# MotorController.net
KiCad netlist of a schematic drawn in EAGLE
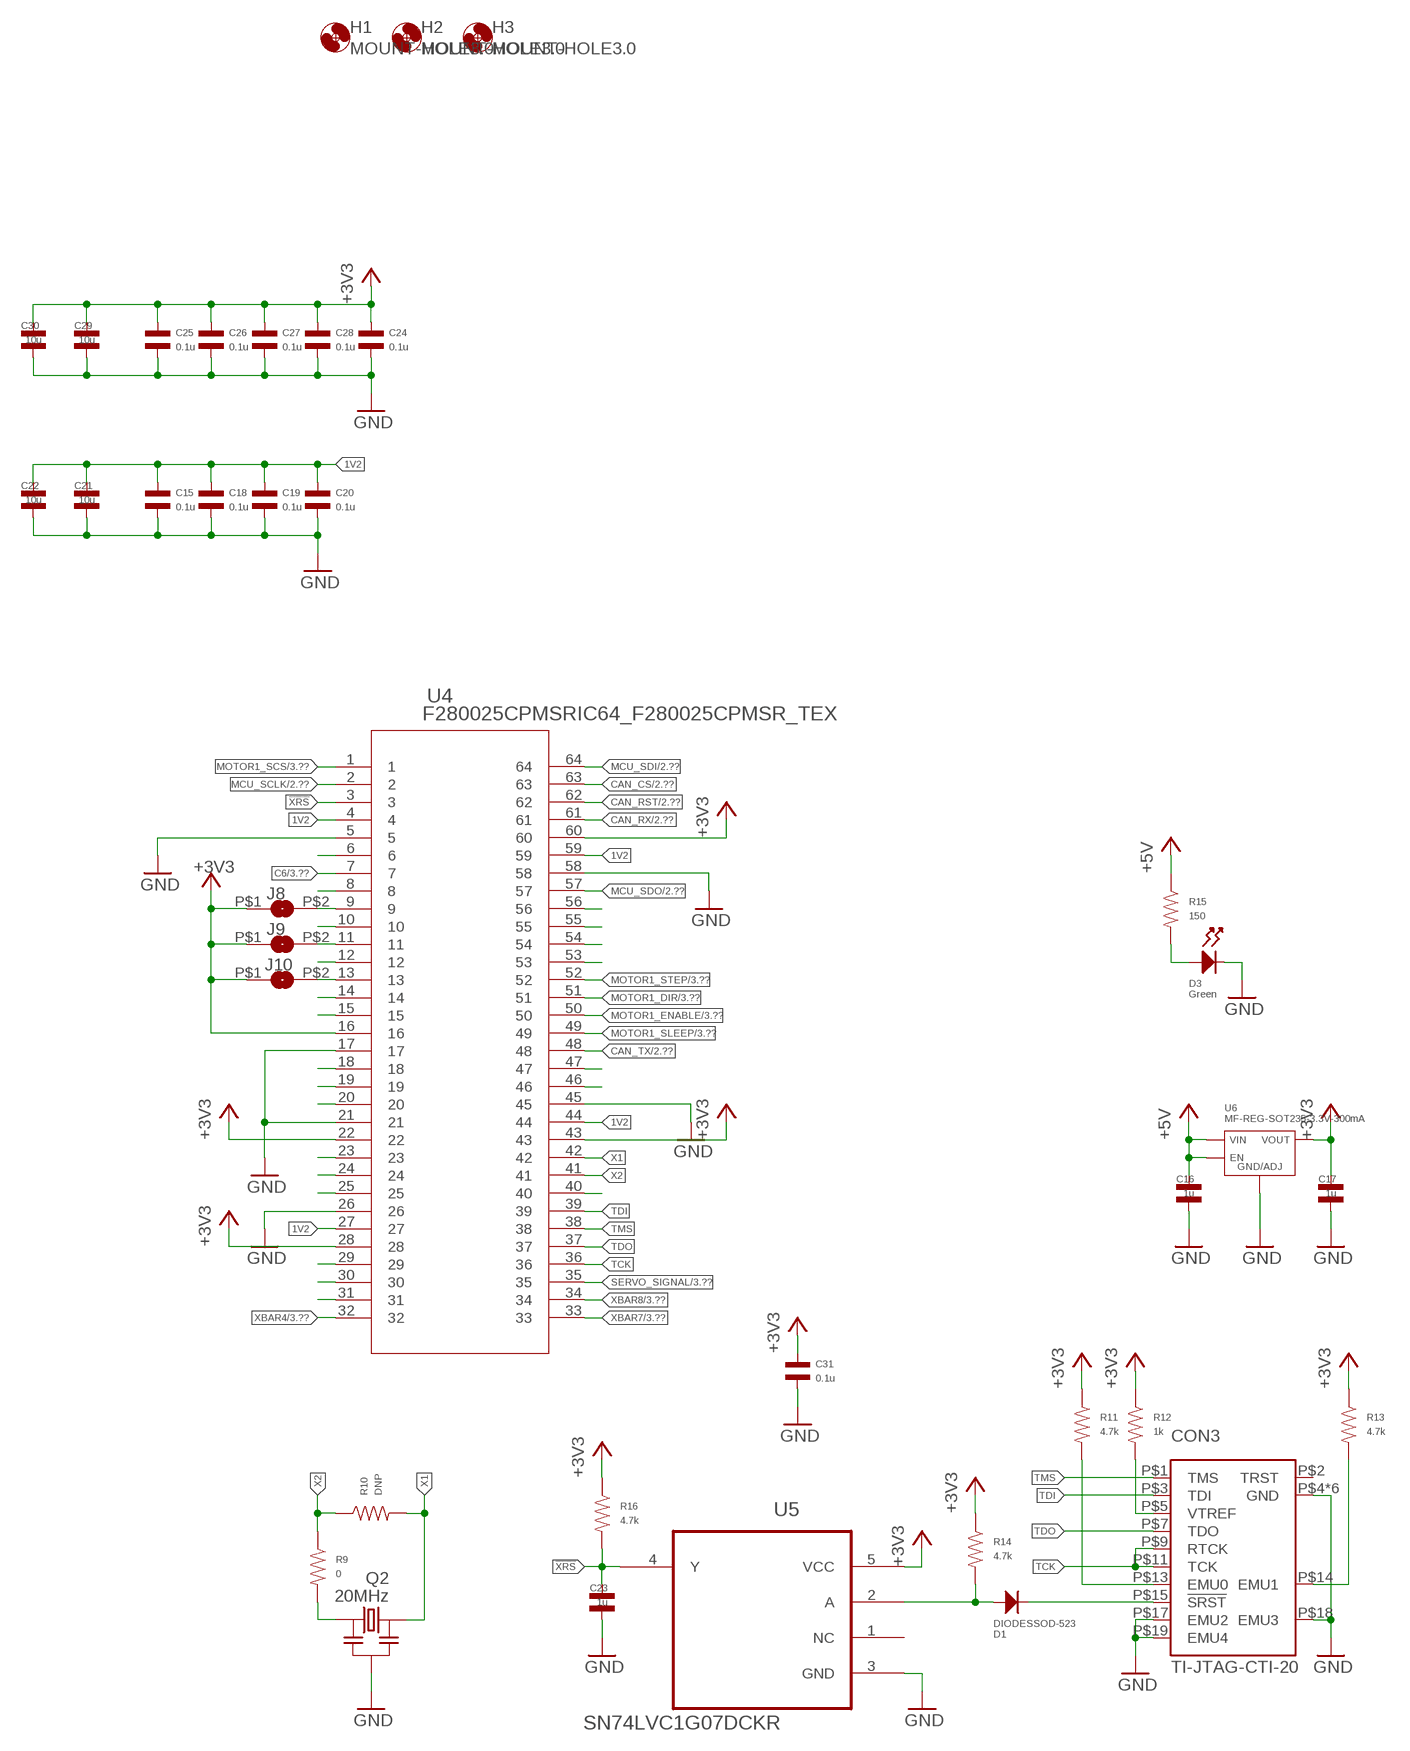
[diagram p0: schematic, sheet 1]
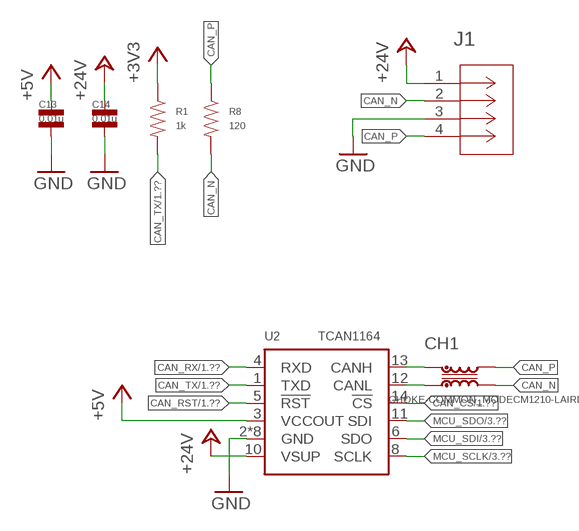
[diagram p1: schematic, sheet 2]
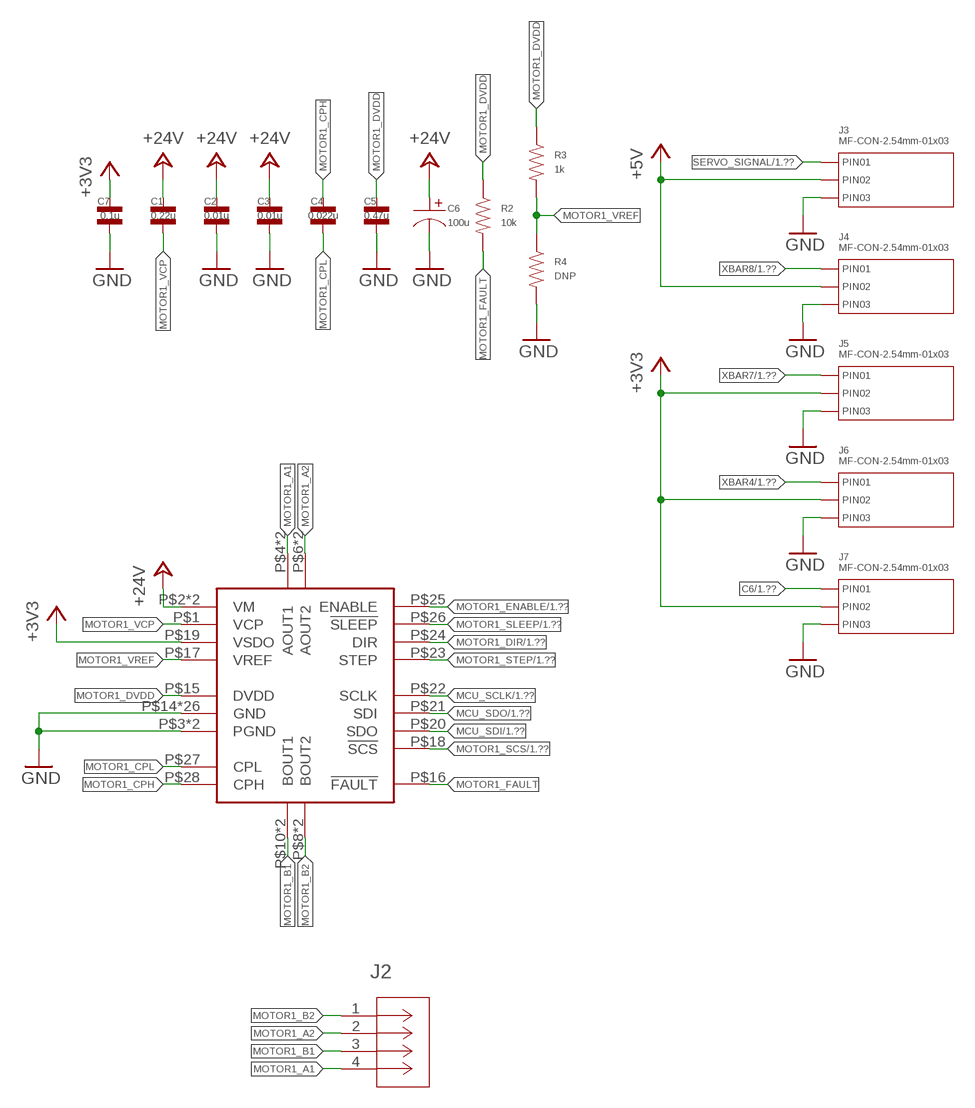
[diagram p2: schematic, sheet 3]

(export (version "E")
  (design (tool "Eeschema 10.0.6"))
  (components
    (comp (ref "C15")
      (value "0.1u")
      (footprint "eagle-import:C0402")
      (fields (field (name "MPN") "GCM155R71H104KE02D"))
      (libsource (lib "eagle-import") (part "CAPACITOR_NP_0402"))
    )
    (comp (ref "C16")
      (value "1u")
      (footprint "eagle-import:C0805")
      (fields (field (name "MPN") "CL21B105KAFNNNE"))
      (libsource (lib "eagle-import") (part "CAPACITOR_NP_0805"))
    )
    (comp (ref "C17")
      (value "1u")
      (footprint "eagle-import:C0805")
      (fields (field (name "MPN") "CL21B105KAFNNNE"))
      (libsource (lib "eagle-import") (part "CAPACITOR_NP_0805"))
    )
    (comp (ref "C18")
      (value "0.1u")
      (footprint "eagle-import:C0402")
      (fields (field (name "MPN") "GCM155R71H104KE02D"))
      (libsource (lib "eagle-import") (part "CAPACITOR_NP_0402"))
    )
    (comp (ref "C19")
      (value "0.1u")
      (footprint "eagle-import:C0402")
      (fields (field (name "MPN") "GCM155R71H104KE02D"))
      (libsource (lib "eagle-import") (part "CAPACITOR_NP_0402"))
    )
    (comp (ref "C20")
      (value "0.1u")
      (footprint "eagle-import:C0402")
      (fields (field (name "MPN") "GCM155R71H104KE02D"))
      (libsource (lib "eagle-import") (part "CAPACITOR_NP_0402"))
    )
    (comp (ref "C21")
      (value "10u")
      (footprint "eagle-import:C0805")
      (fields (field (name "MPN") "CL21A106KAYNNNE"))
      (libsource (lib "eagle-import") (part "CAPACITOR_NP_0805"))
    )
    (comp (ref "C22")
      (value "10u")
      (footprint "eagle-import:C0805")
      (fields (field (name "MPN") "CL21A106KAYNNNE"))
      (libsource (lib "eagle-import") (part "CAPACITOR_NP_0805"))
    )
    (comp (ref "C23")
      (value "1u")
      (footprint "eagle-import:C0402")
      (fields (field (name "MPN") "CL05A105KA5NQNC"))
      (libsource (lib "eagle-import") (part "CAPACITOR_NP_0402"))
    )
    (comp (ref "C24")
      (value "0.1u")
      (footprint "eagle-import:C0402")
      (fields (field (name "MPN") "GCM155R71H104KE02D"))
      (libsource (lib "eagle-import") (part "CAPACITOR_NP_0402"))
    )
    (comp (ref "C25")
      (value "0.1u")
      (footprint "eagle-import:C0402")
      (fields (field (name "MPN") "GCM155R71H104KE02D"))
      (libsource (lib "eagle-import") (part "CAPACITOR_NP_0402"))
    )
    (comp (ref "C26")
      (value "0.1u")
      (footprint "eagle-import:C0402")
      (fields (field (name "MPN") "GCM155R71H104KE02D"))
      (libsource (lib "eagle-import") (part "CAPACITOR_NP_0402"))
    )
    (comp (ref "C27")
      (value "0.1u")
      (footprint "eagle-import:C0402")
      (fields (field (name "MPN") "GCM155R71H104KE02D"))
      (libsource (lib "eagle-import") (part "CAPACITOR_NP_0402"))
    )
    (comp (ref "C28")
      (value "0.1u")
      (footprint "eagle-import:C0402")
      (fields (field (name "MPN") "GCM155R71H104KE02D"))
      (libsource (lib "eagle-import") (part "CAPACITOR_NP_0402"))
    )
    (comp (ref "C29")
      (value "10u")
      (footprint "eagle-import:C0805")
      (fields (field (name "MPN") "CL21A106KAYNNNE"))
      (libsource (lib "eagle-import") (part "CAPACITOR_NP_0805"))
    )
    (comp (ref "C30")
      (value "10u")
      (footprint "eagle-import:C0805")
      (fields (field (name "MPN") "CL21A106KAYNNNE"))
      (libsource (lib "eagle-import") (part "CAPACITOR_NP_0805"))
    )
    (comp (ref "C31")
      (value "0.1u")
      (footprint "eagle-import:C0402")
      (fields (field (name "MPN") "GCM155R71H104KE02D"))
      (libsource (lib "eagle-import") (part "MF_Passives_4704077_CAPACITOR_NP_0402"))
    )
    (comp (ref "CON3")
      (value "TI-JTAG-CTI-20")
      (footprint "eagle-import:FTR-110-51-L-D-06")
      (fields (field (name "MPN") "FTR-110-51-L-D-06"))
      (libsource (lib "eagle-import") (part "TI-JTAG-CTI-20"))
    )
    (comp (ref "D1")
      (value "DIODESSOD-523")
      (footprint "eagle-import:SOD523")
      (fields (field (name "MPN") "RB510SM-40FHT2R"))
      (libsource (lib "eagle-import") (part "DIODESSOD-523"))
    )
    (comp (ref "D3")
      (value "Green")
      (footprint "eagle-import:LED0603")
      (fields (field (name "HOUSEPART") "NO") (field (name "MPN") "SML-E12P8WT86"))
      (libsource (lib "eagle-import") (part "LED_SINGLE-0603"))
    )
    (comp (ref "H1")
      (value "MOUNT-HOLE3.0")
      (footprint "eagle-import:3,0")
      (libsource (lib "eagle-import") (part "MOUNT-HOLE3.0"))
    )
    (comp (ref "H2")
      (value "MOUNT-HOLE3.0")
      (footprint "eagle-import:3,0")
      (libsource (lib "eagle-import") (part "MOUNT-HOLE3.0"))
    )
    (comp (ref "H3")
      (value "MOUNT-HOLE3.0")
      (footprint "eagle-import:3,0")
      (libsource (lib "eagle-import") (part "MOUNT-HOLE3.0"))
    )
    (comp (ref "J8")
      (value "JUMPER")
      (footprint "eagle-import:SJ")
      (libsource (lib "eagle-import") (part "JUMPER"))
    )
    (comp (ref "J9")
      (value "JUMPER")
      (footprint "eagle-import:SJ")
      (libsource (lib "eagle-import") (part "JUMPER"))
    )
    (comp (ref "J10")
      (value "JUMPER")
      (footprint "eagle-import:SJ")
      (libsource (lib "eagle-import") (part "JUMPER"))
    )
    (comp (ref "Q2")
      (value "20MHz")
      (footprint "eagle-import:CSTNE")
      (fields (field (name "MPN") "CSTNE20M0V53C000R0"))
      (libsource (lib "eagle-import") (part "RESONATORCSTNE"))
    )
    (comp (ref "R9")
      (value "0")
      (footprint "eagle-import:R0402")
      (fields (field (name "MPN") "ERJ-2GE0R00X"))
      (libsource (lib "eagle-import") (part "RESISTOR_0402"))
    )
    (comp (ref "R10")
      (value "DNP")
      (footprint "eagle-import:R0402")
      (libsource (lib "eagle-import") (part "RESISTOR_0402"))
    )
    (comp (ref "R11")
      (value "4.7k")
      (footprint "eagle-import:R0402")
      (fields (field (name "MPN") "ERJ-2RKF4701X"))
      (libsource (lib "eagle-import") (part "RESISTOR_0402"))
    )
    (comp (ref "R12")
      (value "1k")
      (footprint "eagle-import:R0402")
      (fields (field (name "MPN") "ERJ-2RKF1001X"))
      (libsource (lib "eagle-import") (part "RESISTOR_0402"))
    )
    (comp (ref "R13")
      (value "4.7k")
      (footprint "eagle-import:R0402")
      (fields (field (name "MPN") "ERJ-2RKF4701X"))
      (libsource (lib "eagle-import") (part "RESISTOR_0402"))
    )
    (comp (ref "R14")
      (value "4.7k")
      (footprint "eagle-import:R0402")
      (fields (field (name "MPN") "ERJ-2RKF4701X"))
      (libsource (lib "eagle-import") (part "RESISTOR_0402"))
    )
    (comp (ref "R15")
      (value "150")
      (footprint "eagle-import:R0805")
      (fields (field (name "MPN") "ERJ-6GEYJ151V"))
      (libsource (lib "eagle-import") (part "RESISTOR_0805"))
    )
    (comp (ref "R16")
      (value "4.7k")
      (footprint "eagle-import:R0402")
      (fields (field (name "MPN") "ERJ-2RKF4701X"))
      (libsource (lib "eagle-import") (part "RESISTOR_0402"))
    )
    (comp (ref "U4")
      (value "F280025CPMSRIC64_F280025CPMSR_TEX")
      (footprint "eagle-import:IC64_F280025CPMSR_TEX")
      (fields
        (field (name "MANUFACTURER_PART_NUMBER") "F280025CPMSR")
        (field (name "COPYRIGHT") "Copyright (C) 2024 Ultra Librarian. All rights reserved.")
      )
      (libsource (lib "eagle-import") (part "F280025CPMSRIC64_F280025CPMSR_TEX"))
    )
    (comp (ref "U5")
      (value "SN74LVC1G07DCKR")
      (footprint "eagle-import:SOT65P210X110-5N")
      (libsource (lib "eagle-import") (part "SN74LVC1G07DCKR"))
    )
    (comp (ref "U6")
      (value "MF-REG-SOT235-3.3V-300mA")
      (footprint "eagle-import:SOT-23-5")
      (fields (field (name "HOUSEPART") "YES") (field (name "MPN") "TLV70233PDBVR"))
      (libsource (lib "eagle-import") (part "TLV70233PDBVR"))
    )
    (comp (ref "C13")
      (value "0.01u")
      (footprint "eagle-import:C0402")
      (fields (field (name "MPN") "CL05B103KB5NNNC"))
      (libsource (lib "eagle-import") (part "CAPACITOR_NP_0402"))
    )
    (comp (ref "C14")
      (value "0.01u")
      (footprint "eagle-import:C0402")
      (fields (field (name "MPN") "CL05B103KB5NNNC"))
      (libsource (lib "eagle-import") (part "CAPACITOR_NP_0402"))
    )
    (comp (ref "CH1")
      (value "CHOKE-COMMON_MODECM1210-LAIRD")
      (footprint "eagle-import:CM1210-LAIRD")
      (fields (field (name "MPN") "CM1210B104R-1A"))
      (libsource (lib "eagle-import") (part "CHOKE-COMMON_MODECM1210-LAIRD"))
    )
    (comp (ref "J1")
      (value "768250004CON_768250004_MOL")
      (footprint "eagle-import:CON_768250004_MOL")
      (fields
        (field (name "MANUFACTURER_PART_NUMBER") "768250004")
        (field (name "MPN") "0768250004")
        (field (name "COPYRIGHT") "Copyright (C) 2024 Ultra Librarian. All rights reserved.")
      )
      (libsource (lib "eagle-import") (part "768250004CON_768250004_MOL"))
    )
    (comp (ref "R1")
      (value "1k")
      (footprint "eagle-import:R0402")
      (fields (field (name "MPN") "ERJ-2RKF1001X"))
      (libsource (lib "eagle-import") (part "RESISTOR_0402"))
    )
    (comp (ref "R8")
      (value "120")
      (footprint "eagle-import:R0402")
      (fields (field (name "MPN") "ERJ-2GEJ121X"))
      (libsource (lib "eagle-import") (part "RESISTOR_0402"))
    )
    (comp (ref "U2")
      (value "TCAN1164")
      (footprint "eagle-import:CONV_TPS63021DSJ")
      (fields (field (name "MPN") "TCAN1164DMTRQ1"))
      (libsource (lib "eagle-import") (part "TCAN1164"))
    )
    (comp (ref "C1")
      (value "0.22u")
      (footprint "eagle-import:C0402")
      (fields (field (name "MPN") "CL05B224KA5VPNC"))
      (libsource (lib "eagle-import") (part "CAPACITOR_NP_0402"))
    )
    (comp (ref "C2")
      (value "0.01u")
      (footprint "eagle-import:C0402")
      (fields (field (name "MPN") "CL05B103KB5NNNC"))
      (libsource (lib "eagle-import") (part "CAPACITOR_NP_0402"))
    )
    (comp (ref "C3")
      (value "0.01u")
      (footprint "eagle-import:C0402")
      (fields (field (name "MPN") "CL05B103KB5NNNC"))
      (libsource (lib "eagle-import") (part "CAPACITOR_NP_0402"))
    )
    (comp (ref "C4")
      (value "0.022u")
      (footprint "eagle-import:C0402")
      (fields (field (name "MPN") "CL05B223KB5VPNC"))
      (libsource (lib "eagle-import") (part "CAPACITOR_NP_0402"))
    )
    (comp (ref "C5")
      (value "0.47u")
      (footprint "eagle-import:C0402")
      (fields (field (name "MPN") "CL05A474KA5NNNC"))
      (libsource (lib "eagle-import") (part "CAPACITOR_NP_0402"))
    )
    (comp (ref "C6")
      (value "100u")
      (footprint "eagle-import:CP6.3MM")
      (fields (field (name "MPN") "MAL218297603E3"))
      (libsource (lib "eagle-import") (part "CAPACITOR_P_6.3MM"))
    )
    (comp (ref "C7")
      (value "0.1u")
      (footprint "eagle-import:C0402")
      (fields (field (name "MPN") "GCM155R71H104KE02D"))
      (libsource (lib "eagle-import") (part "CAPACITOR_NP_0402"))
    )
    (comp (ref "J2")
      (value "768250004CON_768250004_MOL")
      (footprint "eagle-import:CON_768250004_MOL")
      (fields
        (field (name "MANUFACTURER_PART_NUMBER") "768250004")
        (field (name "MPN") "0768250004")
        (field (name "COPYRIGHT") "Copyright (C) 2024 Ultra Librarian. All rights reserved.")
      )
      (libsource (lib "eagle-import") (part "768250004CON_768250004_MOL"))
    )
    (comp (ref "J3")
      (value "MF-CON-2.54mm-01x03")
      (footprint "eagle-import:PTH_2.54MM_01X03")
      (fields (field (name "HOUSEPART") "YES"))
      (libsource (lib "eagle-import") (part "CON_01X03_PTH_2.54MM"))
    )
    (comp (ref "J4")
      (value "MF-CON-2.54mm-01x03")
      (footprint "eagle-import:PTH_2.54MM_01X03")
      (fields (field (name "HOUSEPART") "YES"))
      (libsource (lib "eagle-import") (part "CON_01X03_PTH_2.54MM"))
    )
    (comp (ref "J5")
      (value "MF-CON-2.54mm-01x03")
      (footprint "eagle-import:PTH_2.54MM_01X03")
      (fields (field (name "HOUSEPART") "YES"))
      (libsource (lib "eagle-import") (part "CON_01X03_PTH_2.54MM"))
    )
    (comp (ref "J6")
      (value "MF-CON-2.54mm-01x03")
      (footprint "eagle-import:PTH_2.54MM_01X03")
      (fields (field (name "HOUSEPART") "YES"))
      (libsource (lib "eagle-import") (part "CON_01X03_PTH_2.54MM"))
    )
    (comp (ref "J7")
      (value "MF-CON-2.54mm-01x03")
      (footprint "eagle-import:PTH_2.54MM_01X03")
      (fields (field (name "HOUSEPART") "YES"))
      (libsource (lib "eagle-import") (part "CON_01X03_PTH_2.54MM"))
    )
    (comp (ref "R2")
      (value "10k")
      (footprint "eagle-import:R0402")
      (fields (field (name "MPN") "ERJ-2RKF1002X"))
      (libsource (lib "eagle-import") (part "RESISTOR_0402"))
    )
    (comp (ref "R3")
      (value "1k")
      (footprint "eagle-import:R0402")
      (fields (field (name "MPN") "ERJ-2RKF1001X"))
      (libsource (lib "eagle-import") (part "RESISTOR_0402"))
    )
    (comp (ref "R4")
      (value "DNP")
      (footprint "eagle-import:R0402")
      (libsource (lib "eagle-import") (part "RESISTOR_0402"))
    )
    (comp (ref "U1")
      (value "DRV8434SPWPR")
      (footprint "eagle-import:HTSSOP(PWP)-28")
      (libsource (lib "eagle-import") (part "DRV8434SPWPR"))
    )
  )
  (nets
    (net (code "1") (name "+3V3") (class "Default")
      (node (ref "C17") (pin "P$1") (pinfunction "P$1_P$1") (pintype "passive"))
      (node (ref "C24") (pin "P$1") (pinfunction "P$1_P$1") (pintype "passive"))
      (node (ref "C25") (pin "P$1") (pinfunction "P$1_P$1") (pintype "passive"))
      (node (ref "C26") (pin "P$1") (pinfunction "P$1_P$1") (pintype "passive"))
      (node (ref "C27") (pin "P$1") (pinfunction "P$1_P$1") (pintype "passive"))
      (node (ref "C28") (pin "P$1") (pinfunction "P$1_P$1") (pintype "passive"))
      (node (ref "C29") (pin "P$1") (pinfunction "P$1_P$1") (pintype "passive"))
      (node (ref "C30") (pin "P$1") (pinfunction "P$1_P$1") (pintype "passive"))
      (node (ref "C31") (pin "P$1") (pinfunction "P$1_P$1") (pintype "passive"))
      (node (ref "C7") (pin "P$1") (pinfunction "P$1_P$1") (pintype "passive"))
      (node (ref "J10") (pin "P$1") (pinfunction "1_P$1") (pintype "passive"))
      (node (ref "J5") (pin "P$2") (pinfunction "PIN2_P$2") (pintype "bidirectional"))
      (node (ref "J6") (pin "P$2") (pinfunction "PIN2_P$2") (pintype "bidirectional"))
      (node (ref "J7") (pin "P$2") (pinfunction "PIN2_P$2") (pintype "bidirectional"))
      (node (ref "J8") (pin "P$1") (pinfunction "1_P$1") (pintype "passive"))
      (node (ref "J9") (pin "P$1") (pinfunction "1_P$1") (pintype "passive"))
      (node (ref "R1") (pin "P$1") (pinfunction "P$1_P$1") (pintype "passive"))
      (node (ref "R11") (pin "P$1") (pinfunction "P$1_P$1") (pintype "passive"))
      (node (ref "R12") (pin "P$1") (pinfunction "P$1_P$1") (pintype "passive"))
      (node (ref "R13") (pin "P$1") (pinfunction "P$1_P$1") (pintype "passive"))
      (node (ref "R14") (pin "P$1") (pinfunction "P$1_P$1") (pintype "passive"))
      (node (ref "R16") (pin "P$1") (pinfunction "P$1_P$1") (pintype "passive"))
      (node (ref "U1") (pin "P$19") (pinfunction "VSDO_P$19") (pintype "bidirectional"))
      (node (ref "U4") (pin "16") (pinfunction "16_16") (pintype "passive"))
      (node (ref "U4") (pin "22") (pinfunction "22_22") (pintype "passive"))
      (node (ref "U4") (pin "28") (pinfunction "28_28") (pintype "passive"))
      (node (ref "U4") (pin "43") (pinfunction "43_43") (pintype "passive"))
      (node (ref "U4") (pin "60") (pinfunction "60_60") (pintype "passive"))
      (node (ref "U5") (pin "5") (pinfunction "VCC_5") (pintype "power_in"))
      (node (ref "U6") (pin "P$5") (pinfunction "VOUT_P$5") (pintype "bidirectional"))
    )
    (net (code "2") (name "+5V") (class "Default")
      (node (ref "C13") (pin "P$1") (pinfunction "P$1_P$1") (pintype "passive"))
      (node (ref "C16") (pin "P$1") (pinfunction "P$1_P$1") (pintype "passive"))
      (node (ref "J3") (pin "P$2") (pinfunction "PIN2_P$2") (pintype "bidirectional"))
      (node (ref "J4") (pin "P$2") (pinfunction "PIN2_P$2") (pintype "bidirectional"))
      (node (ref "R15") (pin "P$1") (pinfunction "P$1_P$1") (pintype "passive"))
      (node (ref "U2") (pin "3") (pinfunction "VCCOUT_3") (pintype "bidirectional"))
      (node (ref "U6") (pin "P$1") (pinfunction "VIN_P$1") (pintype "bidirectional"))
      (node (ref "U6") (pin "P$3") (pinfunction "EN_P$3") (pintype "bidirectional"))
    )
    (net (code "3") (name "+24V") (class "Default")
      (node (ref "C1") (pin "P$1") (pinfunction "P$1_P$1") (pintype "passive"))
      (node (ref "C14") (pin "P$1") (pinfunction "P$1_P$1") (pintype "passive"))
      (node (ref "C2") (pin "P$1") (pinfunction "P$1_P$1") (pintype "passive"))
      (node (ref "C3") (pin "P$1") (pinfunction "P$1_P$1") (pintype "passive"))
      (node (ref "C6") (pin "P$1") (pinfunction "P$1_P$1") (pintype "passive"))
      (node (ref "J1") (pin "1") (pinfunction "1_1") (pintype "passive"))
      (node (ref "U1") (pin "P$13") (pinfunction "VM_P$13") (pintype "bidirectional"))
      (node (ref "U1") (pin "P$2") (pinfunction "VM_P$2") (pintype "bidirectional"))
      (node (ref "U2") (pin "10") (pinfunction "VSUP_10") (pintype "bidirectional"))
    )
    (net (code "4") (name "1V2") (class "Default")
      (node (ref "C15") (pin "P$1") (pinfunction "P$1_P$1") (pintype "passive"))
      (node (ref "C18") (pin "P$1") (pinfunction "P$1_P$1") (pintype "passive"))
      (node (ref "C19") (pin "P$1") (pinfunction "P$1_P$1") (pintype "passive"))
      (node (ref "C20") (pin "P$1") (pinfunction "P$1_P$1") (pintype "passive"))
      (node (ref "C21") (pin "P$1") (pinfunction "P$1_P$1") (pintype "passive"))
      (node (ref "C22") (pin "P$1") (pinfunction "P$1_P$1") (pintype "passive"))
      (node (ref "U4") (pin "27") (pinfunction "27_27") (pintype "passive"))
      (node (ref "U4") (pin "4") (pinfunction "4_4") (pintype "passive"))
      (node (ref "U4") (pin "44") (pinfunction "44_44") (pintype "passive"))
      (node (ref "U4") (pin "59") (pinfunction "59_59") (pintype "passive"))
    )
    (net (code "5") (name "C6") (class "Default")
      (node (ref "J7") (pin "P$1") (pinfunction "PIN1_P$1") (pintype "bidirectional"))
      (node (ref "U4") (pin "7") (pinfunction "7_7") (pintype "passive"))
    )
    (net (code "6") (name "CAN_CS") (class "Default")
      (node (ref "U2") (pin "14") (pinfunction "~{CS}_14") (pintype "bidirectional"))
      (node (ref "U4") (pin "63") (pinfunction "63_63") (pintype "passive"))
    )
    (net (code "7") (name "CAN_N") (class "Default")
      (node (ref "CH1") (pin "P$3") (pinfunction "3_P$3") (pintype "bidirectional"))
      (node (ref "J1") (pin "2") (pinfunction "2_2") (pintype "passive"))
      (node (ref "R8") (pin "P$2") (pinfunction "P$2_P$2") (pintype "passive"))
    )
    (net (code "8") (name "CAN_P") (class "Default")
      (node (ref "CH1") (pin "P$2") (pinfunction "2_P$2") (pintype "bidirectional"))
      (node (ref "J1") (pin "4") (pinfunction "4_4") (pintype "passive"))
      (node (ref "R8") (pin "P$1") (pinfunction "P$1_P$1") (pintype "passive"))
    )
    (net (code "9") (name "CAN_RST") (class "Default")
      (node (ref "U2") (pin "5") (pinfunction "~{RST}_5") (pintype "bidirectional"))
      (node (ref "U4") (pin "62") (pinfunction "62_62") (pintype "passive"))
    )
    (net (code "10") (name "CAN_RX") (class "Default")
      (node (ref "U2") (pin "4") (pinfunction "RXD_4") (pintype "bidirectional"))
      (node (ref "U4") (pin "61") (pinfunction "61_61") (pintype "passive"))
    )
    (net (code "11") (name "CAN_TX") (class "Default")
      (node (ref "R1") (pin "P$2") (pinfunction "P$2_P$2") (pintype "passive"))
      (node (ref "U2") (pin "1") (pinfunction "TXD_1") (pintype "bidirectional"))
      (node (ref "U4") (pin "48") (pinfunction "48_48") (pintype "passive"))
    )
    (net (code "12") (name "GND") (class "Default")
      (node (ref "C13") (pin "P$2") (pinfunction "P$2_P$2") (pintype "passive"))
      (node (ref "C14") (pin "P$2") (pinfunction "P$2_P$2") (pintype "passive"))
      (node (ref "C15") (pin "P$2") (pinfunction "P$2_P$2") (pintype "passive"))
      (node (ref "C16") (pin "P$2") (pinfunction "P$2_P$2") (pintype "passive"))
      (node (ref "C17") (pin "P$2") (pinfunction "P$2_P$2") (pintype "passive"))
      (node (ref "C18") (pin "P$2") (pinfunction "P$2_P$2") (pintype "passive"))
      (node (ref "C19") (pin "P$2") (pinfunction "P$2_P$2") (pintype "passive"))
      (node (ref "C2") (pin "P$2") (pinfunction "P$2_P$2") (pintype "passive"))
      (node (ref "C20") (pin "P$2") (pinfunction "P$2_P$2") (pintype "passive"))
      (node (ref "C21") (pin "P$2") (pinfunction "P$2_P$2") (pintype "passive"))
      (node (ref "C22") (pin "P$2") (pinfunction "P$2_P$2") (pintype "passive"))
      (node (ref "C23") (pin "P$2") (pinfunction "P$2_P$2") (pintype "passive"))
      (node (ref "C24") (pin "P$2") (pinfunction "P$2_P$2") (pintype "passive"))
      (node (ref "C25") (pin "P$2") (pinfunction "P$2_P$2") (pintype "passive"))
      (node (ref "C26") (pin "P$2") (pinfunction "P$2_P$2") (pintype "passive"))
      (node (ref "C27") (pin "P$2") (pinfunction "P$2_P$2") (pintype "passive"))
      (node (ref "C28") (pin "P$2") (pinfunction "P$2_P$2") (pintype "passive"))
      (node (ref "C29") (pin "P$2") (pinfunction "P$2_P$2") (pintype "passive"))
      (node (ref "C3") (pin "P$2") (pinfunction "P$2_P$2") (pintype "passive"))
      (node (ref "C30") (pin "P$2") (pinfunction "P$2_P$2") (pintype "passive"))
      (node (ref "C31") (pin "P$2") (pinfunction "P$2_P$2") (pintype "passive"))
      (node (ref "C5") (pin "P$2") (pinfunction "P$2_P$2") (pintype "passive"))
      (node (ref "C6") (pin "P$2") (pinfunction "P$2_P$2") (pintype "passive"))
      (node (ref "C7") (pin "P$2") (pinfunction "P$2_P$2") (pintype "passive"))
      (node (ref "CON3") (pin "P$10") (pinfunction "GND_P$10") (pintype "bidirectional"))
      (node (ref "CON3") (pin "P$12") (pinfunction "GND_P$12") (pintype "bidirectional"))
      (node (ref "CON3") (pin "P$16") (pinfunction "GND_P$16") (pintype "bidirectional"))
      (node (ref "CON3") (pin "P$17") (pinfunction "EMU2_P$17") (pintype "bidirectional"))
      (node (ref "CON3") (pin "P$18") (pinfunction "EMU3_P$18") (pintype "bidirectional"))
      (node (ref "CON3") (pin "P$19") (pinfunction "EMU4_P$19") (pintype "bidirectional"))
      (node (ref "CON3") (pin "P$20") (pinfunction "GND_P$20") (pintype "bidirectional"))
      (node (ref "CON3") (pin "P$4") (pinfunction "GND_P$4") (pintype "bidirectional"))
      (node (ref "CON3") (pin "P$8") (pinfunction "GND_P$8") (pintype "bidirectional"))
      (node (ref "D3") (pin "CATHODE") (pinfunction "CATHODE_CATHODE") (pintype "power_in"))
      (node (ref "J1") (pin "3") (pinfunction "3_3") (pintype "passive"))
      (node (ref "J3") (pin "P$3") (pinfunction "PIN3_P$3") (pintype "bidirectional"))
      (node (ref "J4") (pin "P$3") (pinfunction "PIN3_P$3") (pintype "bidirectional"))
      (node (ref "J5") (pin "P$3") (pinfunction "PIN3_P$3") (pintype "bidirectional"))
      (node (ref "J6") (pin "P$3") (pinfunction "PIN3_P$3") (pintype "bidirectional"))
      (node (ref "J7") (pin "P$3") (pinfunction "PIN3_P$3") (pintype "bidirectional"))
      (node (ref "Q2") (pin "2") (pinfunction "GND_2") (pintype "passive"))
      (node (ref "R4") (pin "P$2") (pinfunction "P$2_P$2") (pintype "passive"))
      (node (ref "U1") (pin "P$12") (pinfunction "PGND_P$12") (pintype "bidirectional"))
      (node (ref "U1") (pin "P$14") (pinfunction "GND_P$14") (pintype "bidirectional"))
      (node (ref "U1") (pin "P$29") (pinfunction "GND_P$29") (pintype "bidirectional"))
      (node (ref "U1") (pin "P$3") (pinfunction "PGND_P$3") (pintype "bidirectional"))
      (node (ref "U1") (pin "P$30") (pinfunction "GND_P$30") (pintype "bidirectional"))
      (node (ref "U1") (pin "P$31") (pinfunction "GND_P$31") (pintype "bidirectional"))
      (node (ref "U1") (pin "P$32") (pinfunction "GND_P$32") (pintype "bidirectional"))
      (node (ref "U1") (pin "P$33") (pinfunction "GND_P$33") (pintype "bidirectional"))
      (node (ref "U1") (pin "P$34") (pinfunction "GND_P$34") (pintype "bidirectional"))
      (node (ref "U1") (pin "P$35") (pinfunction "GND_P$35") (pintype "bidirectional"))
      (node (ref "U1") (pin "P$36") (pinfunction "GND_P$36") (pintype "bidirectional"))
      (node (ref "U1") (pin "P$37") (pinfunction "GND_P$37") (pintype "bidirectional"))
      (node (ref "U1") (pin "P$38") (pinfunction "GND_P$38") (pintype "bidirectional"))
      (node (ref "U1") (pin "P$39") (pinfunction "GND_P$39") (pintype "bidirectional"))
      (node (ref "U1") (pin "P$40") (pinfunction "GND_P$40") (pintype "bidirectional"))
      (node (ref "U1") (pin "P$41") (pinfunction "GND_P$41") (pintype "bidirectional"))
      (node (ref "U1") (pin "P$42") (pinfunction "GND_P$42") (pintype "bidirectional"))
      (node (ref "U1") (pin "P$43") (pinfunction "GND_P$43") (pintype "bidirectional"))
      (node (ref "U1") (pin "P$44") (pinfunction "GND_P$44") (pintype "bidirectional"))
      (node (ref "U1") (pin "P$45") (pinfunction "GND_P$45") (pintype "bidirectional"))
      (node (ref "U1") (pin "P$46") (pinfunction "GND_P$46") (pintype "bidirectional"))
      (node (ref "U1") (pin "P$47") (pinfunction "GND_P$47") (pintype "bidirectional"))
      (node (ref "U1") (pin "P$48") (pinfunction "GND_P$48") (pintype "bidirectional"))
      (node (ref "U1") (pin "P$49") (pinfunction "GND_P$49") (pintype "bidirectional"))
      (node (ref "U1") (pin "P$50") (pinfunction "GND_P$50") (pintype "bidirectional"))
      (node (ref "U1") (pin "P$51") (pinfunction "GND_P$51") (pintype "bidirectional"))
      (node (ref "U1") (pin "P$52") (pinfunction "GND_P$52") (pintype "bidirectional"))
      (node (ref "U1") (pin "P$53") (pinfunction "GND_P$53") (pintype "bidirectional"))
      (node (ref "U2") (pin "15") (pinfunction "GND_15") (pintype "bidirectional"))
      (node (ref "U2") (pin "15_1") (pinfunction "GND_15_1") (pintype "bidirectional"))
      (node (ref "U2") (pin "15_2") (pinfunction "GND_15_2") (pintype "bidirectional"))
      (node (ref "U2") (pin "15_3") (pinfunction "GND_15_3") (pintype "bidirectional"))
      (node (ref "U2") (pin "15_4") (pinfunction "GND_15_4") (pintype "bidirectional"))
      (node (ref "U2") (pin "15_5") (pinfunction "GND_15_5") (pintype "bidirectional"))
      (node (ref "U2") (pin "15_6") (pinfunction "GND_15_6") (pintype "bidirectional"))
      (node (ref "U2") (pin "2") (pinfunction "GND_2") (pintype "bidirectional"))
      (node (ref "U4") (pin "17") (pinfunction "17_17") (pintype "passive"))
      (node (ref "U4") (pin "21") (pinfunction "21_21") (pintype "passive"))
      (node (ref "U4") (pin "26") (pinfunction "26_26") (pintype "passive"))
      (node (ref "U4") (pin "45") (pinfunction "45_45") (pintype "passive"))
      (node (ref "U4") (pin "5") (pinfunction "5_5") (pintype "passive"))
      (node (ref "U4") (pin "58") (pinfunction "58_58") (pintype "passive"))
      (node (ref "U5") (pin "3") (pinfunction "GND_3") (pintype "passive"))
      (node (ref "U6") (pin "P$2") (pinfunction "GND/ADJ_P$2") (pintype "bidirectional"))
    )
    (net (code "13") (name "MCU_SCLK") (class "Default")
      (node (ref "U1") (pin "P$22") (pinfunction "SCLK_P$22") (pintype "bidirectional"))
      (node (ref "U2") (pin "8") (pinfunction "SCLK_8") (pintype "bidirectional"))
      (node (ref "U4") (pin "2") (pinfunction "2_2") (pintype "passive"))
    )
    (net (code "14") (name "MCU_SDI") (class "Default")
      (node (ref "U1") (pin "P$20") (pinfunction "SDO_P$20") (pintype "bidirectional"))
      (node (ref "U2") (pin "6") (pinfunction "SDO_6") (pintype "bidirectional"))
      (node (ref "U4") (pin "64") (pinfunction "64_64") (pintype "passive"))
    )
    (net (code "15") (name "MCU_SDO") (class "Default")
      (node (ref "U1") (pin "P$21") (pinfunction "SDI_P$21") (pintype "bidirectional"))
      (node (ref "U2") (pin "11") (pinfunction "SDI_11") (pintype "bidirectional"))
      (node (ref "U4") (pin "57") (pinfunction "57_57") (pintype "passive"))
    )
    (net (code "16") (name "MOTOR1_A1") (class "Default")
      (node (ref "J2") (pin "4") (pinfunction "4_4") (pintype "passive"))
      (node (ref "U1") (pin "P$4") (pinfunction "AOUT1_P$4") (pintype "bidirectional"))
      (node (ref "U1") (pin "P$5") (pinfunction "AOUT1_P$5") (pintype "bidirectional"))
    )
    (net (code "17") (name "MOTOR1_A2") (class "Default")
      (node (ref "J2") (pin "2") (pinfunction "2_2") (pintype "passive"))
      (node (ref "U1") (pin "P$6") (pinfunction "AOUT2_P$6") (pintype "bidirectional"))
      (node (ref "U1") (pin "P$7") (pinfunction "AOUT2_P$7") (pintype "bidirectional"))
    )
    (net (code "18") (name "MOTOR1_B1") (class "Default")
      (node (ref "J2") (pin "3") (pinfunction "3_3") (pintype "passive"))
      (node (ref "U1") (pin "P$10") (pinfunction "BOUT1_P$10") (pintype "bidirectional"))
      (node (ref "U1") (pin "P$11") (pinfunction "BOUT1_P$11") (pintype "bidirectional"))
    )
    (net (code "19") (name "MOTOR1_B2") (class "Default")
      (node (ref "J2") (pin "1") (pinfunction "1_1") (pintype "passive"))
      (node (ref "U1") (pin "P$8") (pinfunction "BOUT2_P$8") (pintype "bidirectional"))
      (node (ref "U1") (pin "P$9") (pinfunction "BOUT2_P$9") (pintype "bidirectional"))
    )
    (net (code "20") (name "MOTOR1_CPH") (class "Default")
      (node (ref "C4") (pin "P$1") (pinfunction "P$1_P$1") (pintype "passive"))
      (node (ref "U1") (pin "P$28") (pinfunction "CPH_P$28") (pintype "bidirectional"))
    )
    (net (code "21") (name "MOTOR1_CPL") (class "Default")
      (node (ref "C4") (pin "P$2") (pinfunction "P$2_P$2") (pintype "passive"))
      (node (ref "U1") (pin "P$27") (pinfunction "CPL_P$27") (pintype "bidirectional"))
    )
    (net (code "22") (name "MOTOR1_DIR") (class "Default")
      (node (ref "U1") (pin "P$24") (pinfunction "DIR_P$24") (pintype "bidirectional"))
      (node (ref "U4") (pin "51") (pinfunction "51_51") (pintype "passive"))
    )
    (net (code "23") (name "MOTOR1_DVDD") (class "Default")
      (node (ref "C5") (pin "P$1") (pinfunction "P$1_P$1") (pintype "passive"))
      (node (ref "R2") (pin "P$1") (pinfunction "P$1_P$1") (pintype "passive"))
      (node (ref "R3") (pin "P$1") (pinfunction "P$1_P$1") (pintype "passive"))
      (node (ref "U1") (pin "P$15") (pinfunction "DVDD_P$15") (pintype "bidirectional"))
    )
    (net (code "24") (name "MOTOR1_ENABLE") (class "Default")
      (node (ref "U1") (pin "P$25") (pinfunction "ENABLE_P$25") (pintype "bidirectional"))
      (node (ref "U4") (pin "50") (pinfunction "50_50") (pintype "passive"))
    )
    (net (code "25") (name "MOTOR1_FAULT") (class "Default")
      (node (ref "R2") (pin "P$2") (pinfunction "P$2_P$2") (pintype "passive"))
      (node (ref "U1") (pin "P$16") (pinfunction "~{FAULT}_P$16") (pintype "bidirectional"))
    )
    (net (code "26") (name "MOTOR1_SCS") (class "Default")
      (node (ref "U1") (pin "P$18") (pinfunction "~{SCS}_P$18") (pintype "bidirectional"))
      (node (ref "U4") (pin "1") (pinfunction "1_1") (pintype "passive"))
    )
    (net (code "27") (name "MOTOR1_SLEEP") (class "Default")
      (node (ref "U1") (pin "P$26") (pinfunction "~{SLEEP}_P$26") (pintype "bidirectional"))
      (node (ref "U4") (pin "49") (pinfunction "49_49") (pintype "passive"))
    )
    (net (code "28") (name "MOTOR1_STEP") (class "Default")
      (node (ref "U1") (pin "P$23") (pinfunction "STEP_P$23") (pintype "bidirectional"))
      (node (ref "U4") (pin "52") (pinfunction "52_52") (pintype "passive"))
    )
    (net (code "29") (name "MOTOR1_VCP") (class "Default")
      (node (ref "C1") (pin "P$2") (pinfunction "P$2_P$2") (pintype "passive"))
      (node (ref "U1") (pin "P$1") (pinfunction "VCP_P$1") (pintype "bidirectional"))
    )
    (net (code "30") (name "MOTOR1_VREF") (class "Default")
      (node (ref "R3") (pin "P$2") (pinfunction "P$2_P$2") (pintype "passive"))
      (node (ref "R4") (pin "P$1") (pinfunction "P$1_P$1") (pintype "passive"))
      (node (ref "U1") (pin "P$17") (pinfunction "VREF_P$17") (pintype "bidirectional"))
    )
    (net (code "31") (name "Net-(CH1-1)") (class "Default")
      (node (ref "CH1") (pin "P$1") (pinfunction "1_P$1") (pintype "bidirectional"))
      (node (ref "U2") (pin "13") (pinfunction "CANH_13") (pintype "bidirectional"))
    )
    (net (code "32") (name "Net-(CH1-4)") (class "Default")
      (node (ref "CH1") (pin "P$4") (pinfunction "4_P$4") (pintype "bidirectional"))
      (node (ref "U2") (pin "12") (pinfunction "CANL_12") (pintype "bidirectional"))
    )
    (net (code "33") (name "Net-(CON3-EMU0)") (class "Default")
      (node (ref "CON3") (pin "P$13") (pinfunction "EMU0_P$13") (pintype "bidirectional"))
      (node (ref "R11") (pin "P$2") (pinfunction "P$2_P$2") (pintype "passive"))
    )
    (net (code "34") (name "Net-(CON3-EMU1)") (class "Default")
      (node (ref "CON3") (pin "P$14") (pinfunction "EMU1_P$14") (pintype "bidirectional"))
      (node (ref "R13") (pin "P$2") (pinfunction "P$2_P$2") (pintype "passive"))
    )
    (net (code "35") (name "Net-(CON3-VTREF)") (class "Default")
      (node (ref "CON3") (pin "P$5") (pinfunction "VTREF_P$5") (pintype "bidirectional"))
      (node (ref "R12") (pin "P$2") (pinfunction "P$2_P$2") (pintype "passive"))
    )
    (net (code "36") (name "Net-(CON3-~{SRST})") (class "Default")
      (node (ref "CON3") (pin "P$15") (pinfunction "~{SRST}_P$15") (pintype "bidirectional"))
      (node (ref "D1") (pin "C") (pinfunction "CATHODE_C") (pintype "bidirectional"))
    )
    (net (code "37") (name "Net-(D1-ANODE)") (class "Default")
      (node (ref "D1") (pin "A") (pinfunction "ANODE_A") (pintype "bidirectional"))
      (node (ref "R14") (pin "P$2") (pinfunction "P$2_P$2") (pintype "passive"))
      (node (ref "U5") (pin "2") (pinfunction "A_2") (pintype "input"))
    )
    (net (code "38") (name "Net-(D3-PadANODE)") (class "Default")
      (node (ref "D3") (pin "ANODE") (pinfunction "ANODE_ANODE") (pintype "power_in"))
      (node (ref "R15") (pin "P$2") (pinfunction "P$2_P$2") (pintype "passive"))
    )
    (net (code "39") (name "Net-(J8-2)") (class "Default")
      (node (ref "J8") (pin "P$2") (pinfunction "2_P$2") (pintype "passive"))
      (node (ref "U4") (pin "9") (pinfunction "9_9") (pintype "passive"))
    )
    (net (code "40") (name "Net-(J9-2)") (class "Default")
      (node (ref "J9") (pin "P$2") (pinfunction "2_P$2") (pintype "passive"))
      (node (ref "U4") (pin "11") (pinfunction "11_11") (pintype "passive"))
    )
    (net (code "41") (name "Net-(J10-2)") (class "Default")
      (node (ref "J10") (pin "P$2") (pinfunction "2_P$2") (pintype "passive"))
      (node (ref "U4") (pin "13") (pinfunction "13_13") (pintype "passive"))
    )
    (net (code "42") (name "Net-(Q2-XOUT)") (class "Default")
      (node (ref "Q2") (pin "3") (pinfunction "XOUT_3") (pintype "passive"))
      (node (ref "R9") (pin "P$2") (pinfunction "P$2_P$2") (pintype "passive"))
    )
    (net (code "43") (name "SERVO_SIGNAL") (class "Default")
      (node (ref "J3") (pin "P$1") (pinfunction "PIN1_P$1") (pintype "bidirectional"))
      (node (ref "U4") (pin "35") (pinfunction "35_35") (pintype "passive"))
    )
    (net (code "44") (name "TCK") (class "Default")
      (node (ref "CON3") (pin "P$11") (pinfunction "TCK_P$11") (pintype "bidirectional"))
      (node (ref "CON3") (pin "P$9") (pinfunction "RTCK_P$9") (pintype "bidirectional"))
      (node (ref "U4") (pin "36") (pinfunction "36_36") (pintype "passive"))
    )
    (net (code "45") (name "TDI") (class "Default")
      (node (ref "CON3") (pin "P$3") (pinfunction "TDI_P$3") (pintype "bidirectional"))
      (node (ref "U4") (pin "39") (pinfunction "39_39") (pintype "passive"))
    )
    (net (code "46") (name "TDO") (class "Default")
      (node (ref "CON3") (pin "P$7") (pinfunction "TDO_P$7") (pintype "bidirectional"))
      (node (ref "U4") (pin "37") (pinfunction "37_37") (pintype "passive"))
    )
    (net (code "47") (name "TMS") (class "Default")
      (node (ref "CON3") (pin "P$1") (pinfunction "TMS_P$1") (pintype "bidirectional"))
      (node (ref "U4") (pin "38") (pinfunction "38_38") (pintype "passive"))
    )
    (net (code "48") (name "X1") (class "Default")
      (node (ref "Q2") (pin "1") (pinfunction "XIN_1") (pintype "passive"))
      (node (ref "R10") (pin "P$2") (pinfunction "P$2_P$2") (pintype "passive"))
      (node (ref "U4") (pin "42") (pinfunction "42_42") (pintype "passive"))
    )
    (net (code "49") (name "X2") (class "Default")
      (node (ref "R10") (pin "P$1") (pinfunction "P$1_P$1") (pintype "passive"))
      (node (ref "R9") (pin "P$1") (pinfunction "P$1_P$1") (pintype "passive"))
      (node (ref "U4") (pin "41") (pinfunction "41_41") (pintype "passive"))
    )
    (net (code "50") (name "XBAR4") (class "Default")
      (node (ref "J6") (pin "P$1") (pinfunction "PIN1_P$1") (pintype "bidirectional"))
      (node (ref "U4") (pin "32") (pinfunction "32_32") (pintype "passive"))
    )
    (net (code "51") (name "XBAR7") (class "Default")
      (node (ref "J5") (pin "P$1") (pinfunction "PIN1_P$1") (pintype "bidirectional"))
      (node (ref "U4") (pin "33") (pinfunction "33_33") (pintype "passive"))
    )
    (net (code "52") (name "XBAR8") (class "Default")
      (node (ref "J4") (pin "P$1") (pinfunction "PIN1_P$1") (pintype "bidirectional"))
      (node (ref "U4") (pin "34") (pinfunction "34_34") (pintype "passive"))
    )
    (net (code "53") (name "unconnected-(CON3-TRST-PadP$2)") (class "Default")
      (node (ref "CON3") (pin "P$2") (pinfunction "TRST_P$2") (pintype "bidirectional"))
    )
    (net (code "54") (name "unconnected-(U4-Pad6)") (class "Default")
      (node (ref "U4") (pin "6") (pinfunction "6_6") (pintype "passive"))
    )
    (net (code "55") (name "unconnected-(U4-Pad8)") (class "Default")
      (node (ref "U4") (pin "8") (pinfunction "8_8") (pintype "passive"))
    )
    (net (code "56") (name "unconnected-(U4-Pad10)") (class "Default")
      (node (ref "U4") (pin "10") (pinfunction "10_10") (pintype "passive"))
    )
    (net (code "57") (name "unconnected-(U4-Pad12)") (class "Default")
      (node (ref "U4") (pin "12") (pinfunction "12_12") (pintype "passive"))
    )
    (net (code "58") (name "unconnected-(U4-Pad14)") (class "Default")
      (node (ref "U4") (pin "14") (pinfunction "14_14") (pintype "passive"))
    )
    (net (code "59") (name "unconnected-(U4-Pad15)") (class "Default")
      (node (ref "U4") (pin "15") (pinfunction "15_15") (pintype "passive"))
    )
    (net (code "60") (name "unconnected-(U4-Pad18)") (class "Default")
      (node (ref "U4") (pin "18") (pinfunction "18_18") (pintype "passive"))
    )
    (net (code "61") (name "unconnected-(U4-Pad19)") (class "Default")
      (node (ref "U4") (pin "19") (pinfunction "19_19") (pintype "passive"))
    )
    (net (code "62") (name "unconnected-(U4-Pad20)") (class "Default")
      (node (ref "U4") (pin "20") (pinfunction "20_20") (pintype "passive"))
    )
    (net (code "63") (name "unconnected-(U4-Pad23)") (class "Default")
      (node (ref "U4") (pin "23") (pinfunction "23_23") (pintype "passive"))
    )
    (net (code "64") (name "unconnected-(U4-Pad24)") (class "Default")
      (node (ref "U4") (pin "24") (pinfunction "24_24") (pintype "passive"))
    )
    (net (code "65") (name "unconnected-(U4-Pad25)") (class "Default")
      (node (ref "U4") (pin "25") (pinfunction "25_25") (pintype "passive"))
    )
    (net (code "66") (name "unconnected-(U4-Pad29)") (class "Default")
      (node (ref "U4") (pin "29") (pinfunction "29_29") (pintype "passive"))
    )
    (net (code "67") (name "unconnected-(U4-Pad30)") (class "Default")
      (node (ref "U4") (pin "30") (pinfunction "30_30") (pintype "passive"))
    )
    (net (code "68") (name "unconnected-(U4-Pad31)") (class "Default")
      (node (ref "U4") (pin "31") (pinfunction "31_31") (pintype "passive"))
    )
    (net (code "69") (name "unconnected-(U4-Pad40)") (class "Default")
      (node (ref "U4") (pin "40") (pinfunction "40_40") (pintype "passive"))
    )
    (net (code "70") (name "unconnected-(U4-Pad46)") (class "Default")
      (node (ref "U4") (pin "46") (pinfunction "46_46") (pintype "passive"))
    )
    (net (code "71") (name "unconnected-(U4-Pad47)") (class "Default")
      (node (ref "U4") (pin "47") (pinfunction "47_47") (pintype "passive"))
    )
    (net (code "72") (name "unconnected-(U4-Pad53)") (class "Default")
      (node (ref "U4") (pin "53") (pinfunction "53_53") (pintype "passive"))
    )
    (net (code "73") (name "unconnected-(U4-Pad54)") (class "Default")
      (node (ref "U4") (pin "54") (pinfunction "54_54") (pintype "passive"))
    )
    (net (code "74") (name "unconnected-(U4-Pad55)") (class "Default")
      (node (ref "U4") (pin "55") (pinfunction "55_55") (pintype "passive"))
    )
    (net (code "75") (name "unconnected-(U4-Pad56)") (class "Default")
      (node (ref "U4") (pin "56") (pinfunction "56_56") (pintype "passive"))
    )
    (net (code "76") (name "unconnected-(U5-NC-Pad1)") (class "Default")
      (node (ref "U5") (pin "1") (pinfunction "NC_1") (pintype "no_connect"))
    )
    (net (code "77") (name "~{XRS}") (class "Default")
      (node (ref "C23") (pin "P$1") (pinfunction "P$1_P$1") (pintype "passive"))
      (node (ref "R16") (pin "P$2") (pinfunction "P$2_P$2") (pintype "passive"))
      (node (ref "U4") (pin "3") (pinfunction "3_3") (pintype "passive"))
      (node (ref "U5") (pin "4") (pinfunction "Y_4") (pintype "output"))
    )
  )
)
